# SCH_NFC-CARD_2024-04-05.net
KiCad netlist of a schematic drawn in EasyEDA
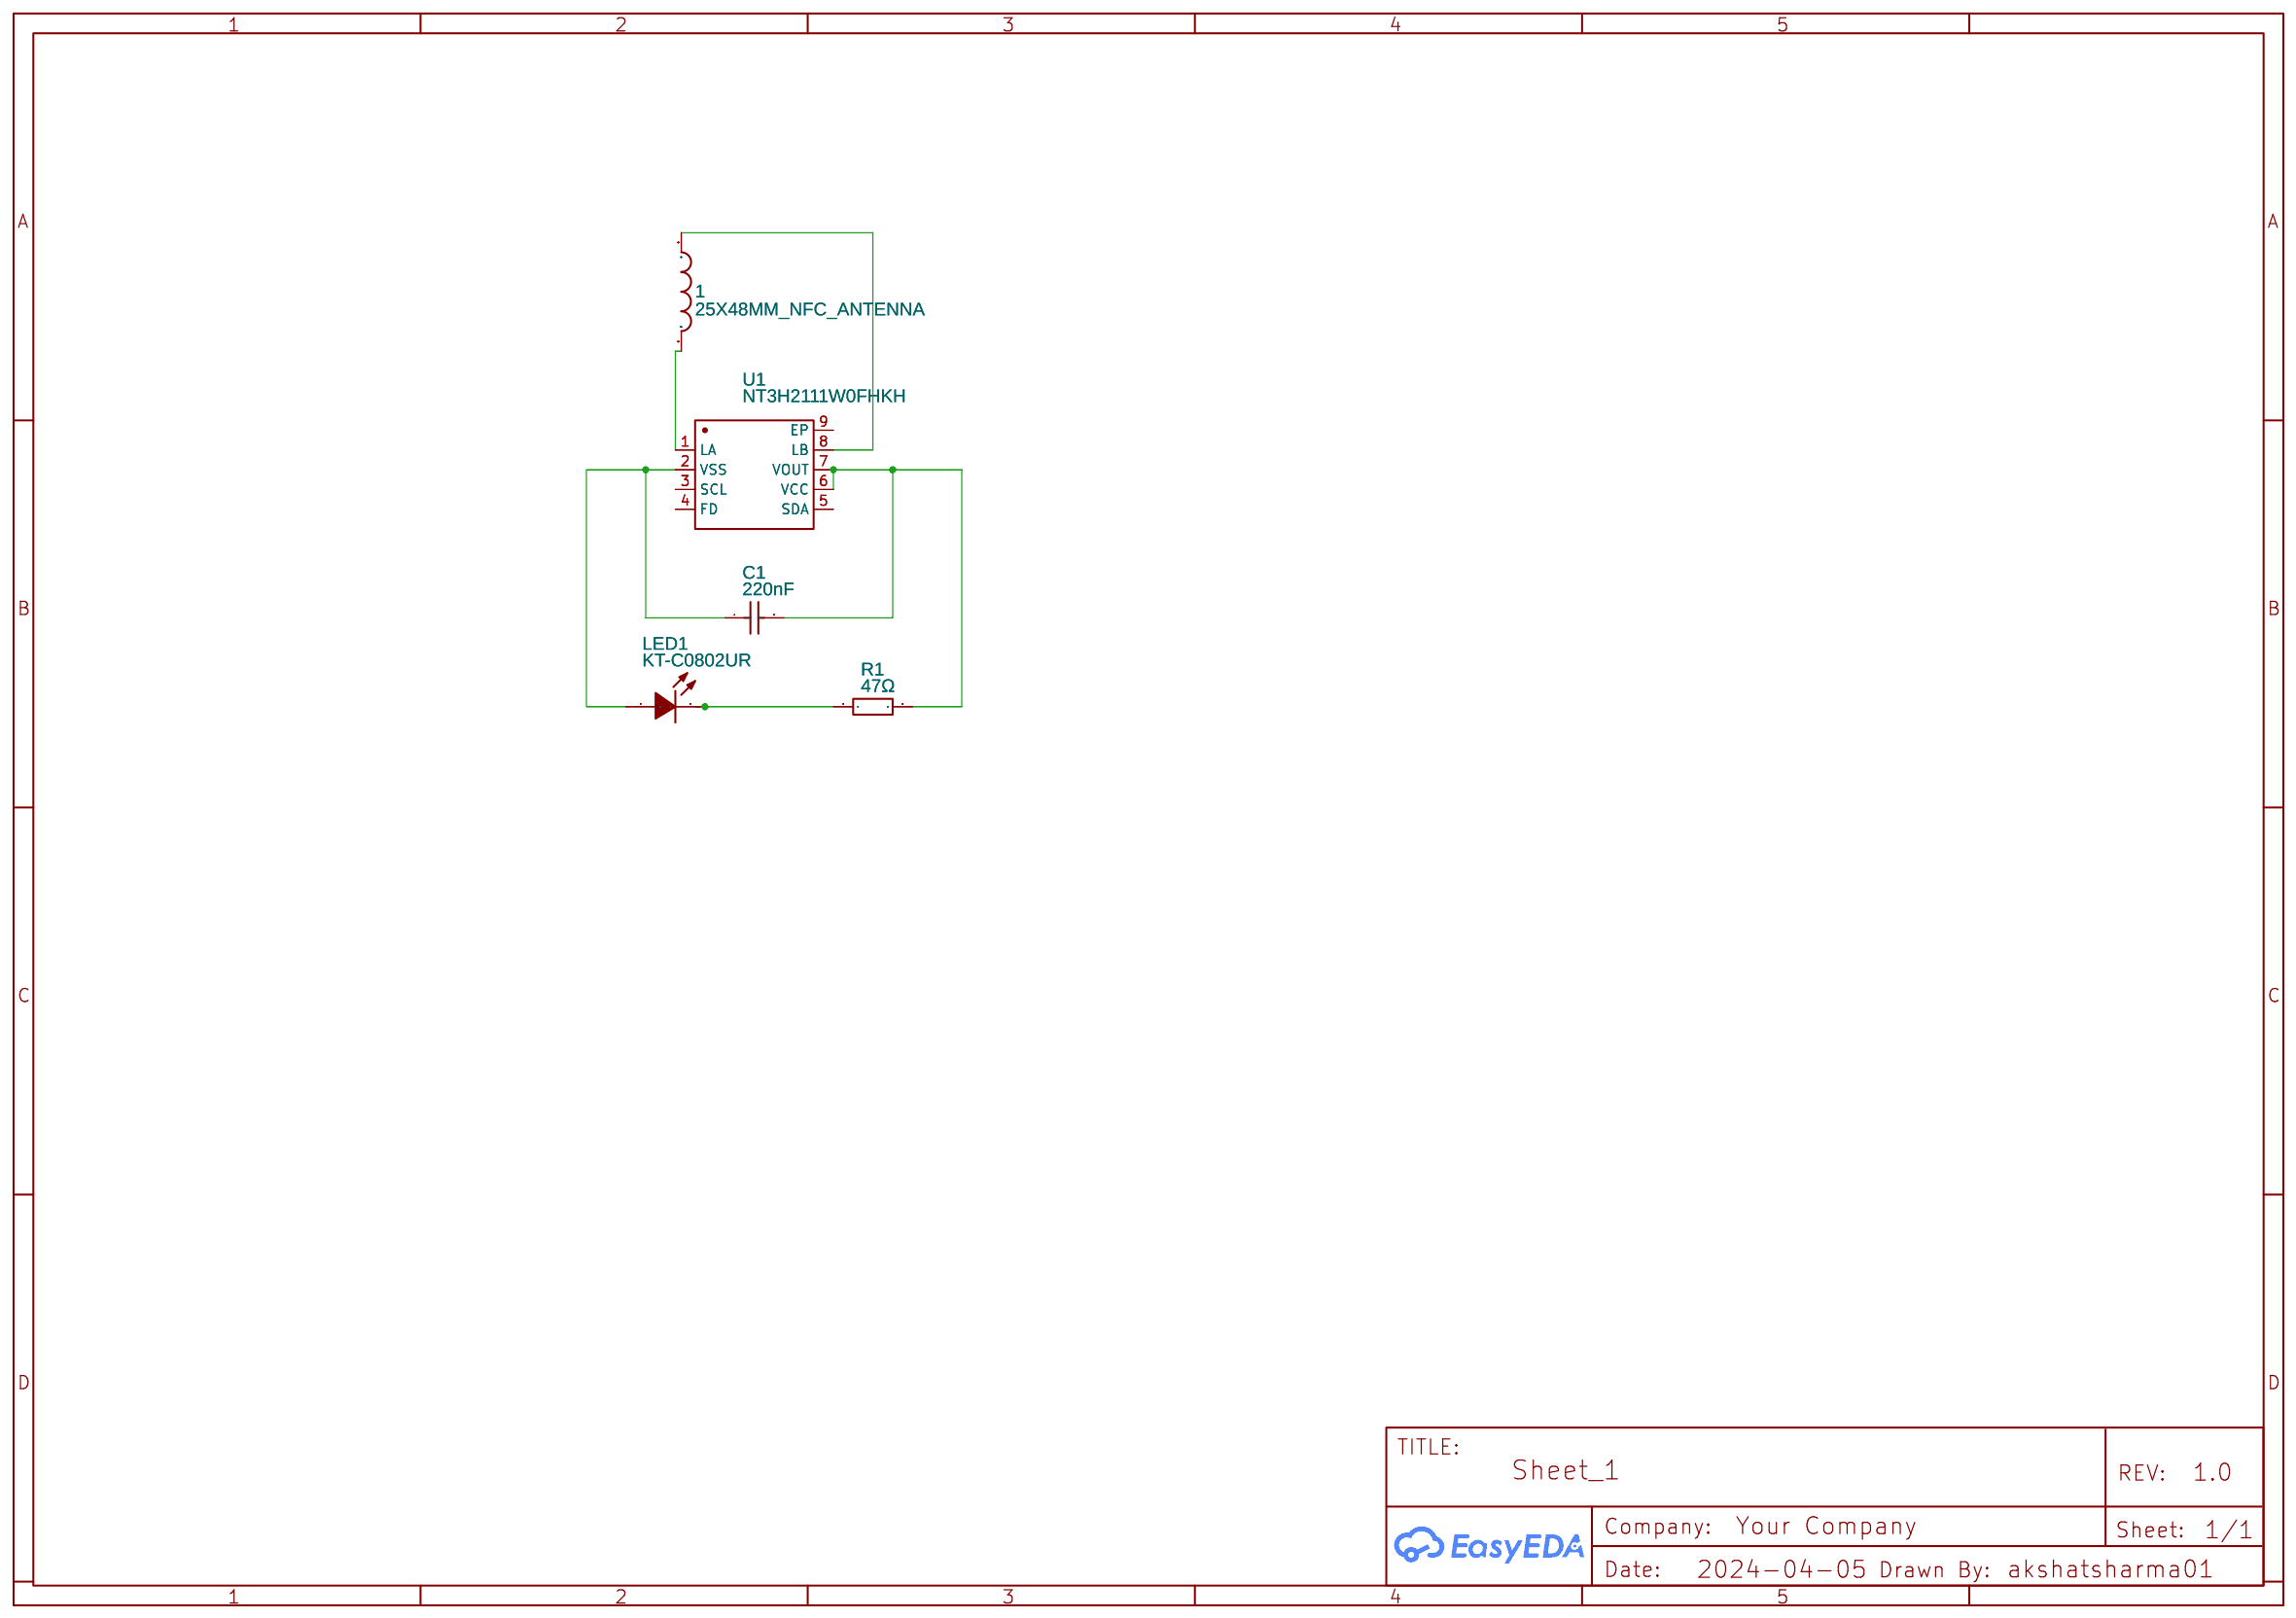
[diagram p0: schematic sheet]

(export (version "E")
  (design (tool "Eeschema 10.0.6"))
  (components
    (comp (ref "1") (value "25X48MM_NFC_ANTENNA") (libsource (lib "") (part "25X48MM_NFC_ANTENNA")))
    (comp (ref "C1")
      (value "220nF")
      (fields
        (field (name "Manufacturer Part") "CL10B224KA8NNNC")
        (field (name "Manufacturer") "SAMSUNG(三星)")
      )
      (libsource (lib "") (part "CL10B224KA8NNNC"))
    )
    (comp (ref "LED1")
      (value "KT-C0802UR")
      (fields (field (name "Manufacturer") "Hubei KENTO Elec"))
      (libsource (lib "") (part "KT-C0802UR"))
    )
    (comp (ref "R1")
      (value "47Ω")
      (fields
        (field (name "Manufacturer Part") "0603WAF470JT5E")
        (field (name "Manufacturer") "UNI-ROYAL(厚声)")
      )
      (libsource (lib "") (part "0603WAF470JT5E"))
    )
    (comp (ref "U1")
      (value "NT3H2111W0FHKH")
      (fields (field (name "Manufacturer") "NXP(恩智浦)"))
      (libsource (lib "") (part "NT3H2111W0FHKH"))
    )
  )
  (nets
    (net (code "1") (name "Net-(LED1-A)") (class "Default")
      (node (ref "C1") (pin "1") (pinfunction "1_1") (pintype "input"))
      (node (ref "LED1") (pin "1") (pinfunction "A_1") (pintype "unspecified"))
      (node (ref "U1") (pin "2") (pinfunction "VSS_2") (pintype "unspecified"))
    )
    (net (code "2") (name "Net-(LED1-K)") (class "Default")
      (node (ref "LED1") (pin "2") (pinfunction "K_2") (pintype "unspecified"))
      (node (ref "R1") (pin "1") (pinfunction "1_1") (pintype "input"))
    )
    (net (code "3") (name "Net-(U1-LA)") (class "Default")
      (node (ref "1") (pin "P$2") (pinfunction "P$2_P$2") (pintype "bidirectional"))
      (node (ref "U1") (pin "1") (pinfunction "LA_1") (pintype "unspecified"))
    )
    (net (code "4") (name "Net-(U1-LB)") (class "Default")
      (node (ref "1") (pin "P$1") (pinfunction "P$1_P$1") (pintype "bidirectional"))
      (node (ref "U1") (pin "8") (pinfunction "LB_8") (pintype "unspecified"))
    )
    (net (code "5") (name "Net-(U1-VCC)") (class "Default")
      (node (ref "C1") (pin "2") (pinfunction "2_2") (pintype "input"))
      (node (ref "R1") (pin "2") (pinfunction "2_2") (pintype "input"))
      (node (ref "U1") (pin "6") (pinfunction "VCC_6") (pintype "unspecified"))
      (node (ref "U1") (pin "7") (pinfunction "VOUT_7") (pintype "unspecified"))
    )
    (net (code "6") (name "unconnected-(U1-EP-Pad9)") (class "Default")
      (node (ref "U1") (pin "9") (pinfunction "EP_9") (pintype "unspecified"))
    )
    (net (code "7") (name "unconnected-(U1-FD-Pad4)") (class "Default")
      (node (ref "U1") (pin "4") (pinfunction "FD_4") (pintype "unspecified"))
    )
    (net (code "8") (name "unconnected-(U1-SCL-Pad3)") (class "Default")
      (node (ref "U1") (pin "3") (pinfunction "SCL_3") (pintype "unspecified"))
    )
    (net (code "9") (name "unconnected-(U1-SDA-Pad5)") (class "Default")
      (node (ref "U1") (pin "5") (pinfunction "SDA_5") (pintype "unspecified"))
    )
  )
)
